# CDU.net
KiCad netlist of a schematic drawn in EAGLE
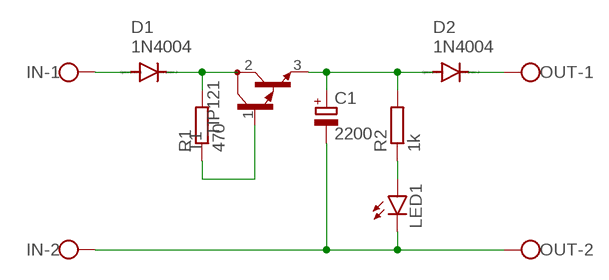
[diagram p0: schematic, sheet 1]

(export (version "E")
  (design (tool "Eeschema 10.0.6"))
  (components
    (comp (ref "C1")
      (value "2200")
      (footprint "eagle-import:E7,5-18")
      (libsource (lib "eagle-import") (part "CPOL-EUE7.5-18"))
    )
    (comp (ref "D1")
      (value "1N4004")
      (footprint "eagle-import:DO41-10")
      (libsource (lib "eagle-import") (part "1N4004"))
    )
    (comp (ref "D2")
      (value "1N4004")
      (footprint "eagle-import:DO41-10")
      (libsource (lib "eagle-import") (part "1N4004"))
    )
    (comp (ref "IN")
      (value "W237-102")
      (footprint "eagle-import:W237-102")
      (fields (field (name "MPN") "237-102"))
      (libsource (lib "eagle-import") (part "W237-102"))
    )
    (comp (ref "LED1")
      (value "LED5MM")
      (footprint "eagle-import:LED5MM")
      (libsource (lib "eagle-import") (part "LED5MM"))
    )
    (comp (ref "OUT")
      (value "W237-102")
      (footprint "eagle-import:W237-102")
      (fields (field (name "MPN") "237-102"))
      (libsource (lib "eagle-import") (part "W237-102"))
    )
    (comp (ref "R1")
      (value "470")
      (footprint "eagle-import:0411_15")
      (libsource (lib "eagle-import") (part "R-EU_0411/15"))
    )
    (comp (ref "R2")
      (value "1k")
      (footprint "eagle-import:0207_10")
      (libsource (lib "eagle-import") (part "R-EU_0207/10"))
    )
    (comp (ref "T1")
      (value "TIP121")
      (footprint "eagle-import:TO220V")
      (libsource (lib "eagle-import") (part "TIP121"))
    )
  )
  (nets
    (net (code "1") (name "Net-(INA-KL)") (class "Default")
      (node (ref "D1") (pin "A") (pinfunction "A_A") (pintype "passive"))
      (node (ref "IN") (pin "1") (pinfunction "KL_1") (pintype "passive"))
    )
    (net (code "2") (name "Net-(INB-KL)") (class "Default")
      (node (ref "C1") (pin "-") (pinfunction "-_-") (pintype "passive"))
      (node (ref "IN") (pin "2") (pinfunction "KL_2") (pintype "passive"))
      (node (ref "LED1") (pin "K") (pinfunction "C_K") (pintype "passive"))
      (node (ref "OUT") (pin "2") (pinfunction "KL_2") (pintype "passive"))
    )
    (net (code "3") (name "Net-(LED1-PadA)") (class "Default")
      (node (ref "LED1") (pin "A") (pinfunction "A_A") (pintype "passive"))
      (node (ref "R2") (pin "1") (pinfunction "1_1") (pintype "passive"))
    )
    (net (code "4") (name "Net-(OUTA-KL)") (class "Default")
      (node (ref "D2") (pin "C") (pinfunction "C_C") (pintype "passive"))
      (node (ref "OUT") (pin "1") (pinfunction "KL_1") (pintype "passive"))
    )
    (net (code "5") (name "Net-(T1-B)") (class "Default")
      (node (ref "R1") (pin "1") (pinfunction "1_1") (pintype "passive"))
      (node (ref "T1") (pin "1") (pinfunction "B_1") (pintype "passive"))
    )
    (net (code "6") (name "Net-(T1-C)") (class "Default")
      (node (ref "D1") (pin "C") (pinfunction "C_C") (pintype "passive"))
      (node (ref "R1") (pin "2") (pinfunction "2_2") (pintype "passive"))
      (node (ref "T1") (pin "2") (pinfunction "C_2") (pintype "passive"))
    )
    (net (code "7") (name "Net-(T1-E)") (class "Default")
      (node (ref "C1") (pin "+") (pinfunction "+_+") (pintype "passive"))
      (node (ref "D2") (pin "A") (pinfunction "A_A") (pintype "passive"))
      (node (ref "R2") (pin "2") (pinfunction "2_2") (pintype "passive"))
      (node (ref "T1") (pin "3") (pinfunction "E_3") (pintype "passive"))
    )
  )
)
